# Sheet2.net
KiCad netlist of a schematic drawn in Altium Designer
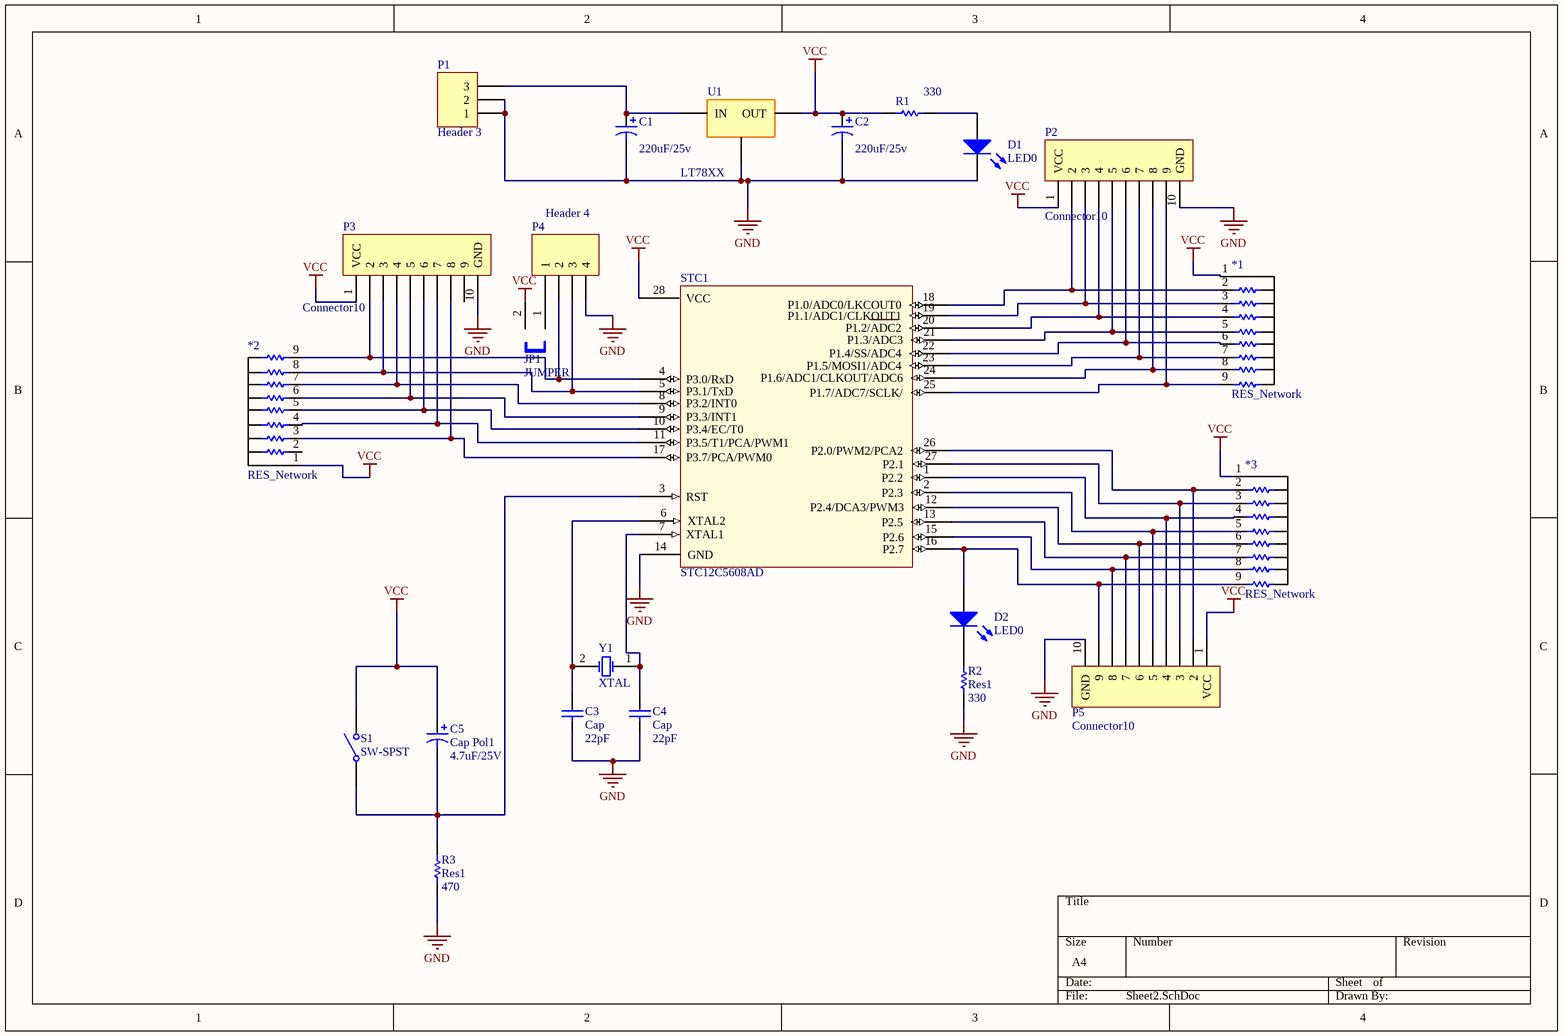
[diagram p0: Sheet2.SchDoc]

(export (version "E")
  (design (tool "Eeschema 10.0.6"))
  (components
    (comp (ref "*1")
      (value "RES_Network")
      (footprint "RES_Network")
      (libsource (lib "Schlib2") (part "RES_Network"))
    )
    (comp (ref "*2")
      (value "RES_Network")
      (footprint "RES_Network")
      (libsource (lib "Schlib2") (part "RES_Network"))
    )
    (comp (ref "*3")
      (value "RES_Network")
      (footprint "RES_Network")
      (libsource (lib "Schlib2") (part "RES_Network"))
    )
    (comp (ref "C1")
      (value "220uF/25v")
      (footprint "CAPA2.5EB")
      (description "Polarized Capacitor (Surface Mount)")
      (fields (field (name "Comment") "Cap Pol3") (field (name "PUBLISHER") "Altium Limited"))
      (libsource (lib "Miscellaneous Devices") (part "Cap Pol3"))
    )
    (comp (ref "C2")
      (value "220uF/25v")
      (footprint "CAPA2.5EB")
      (description "Polarized Capacitor (Surface Mount)")
      (fields (field (name "Comment") "Cap Pol3") (field (name "PUBLISHER") "Altium Limited"))
      (libsource (lib "Miscellaneous Devices") (part "Cap Pol3"))
    )
    (comp (ref "C3")
      (value "Cap")
      (footprint "cap2.5mmceramic")
      (description "Capacitor")
      (fields (field (name "ALTIUM_VALUE") "22pF") (field (name "PUBLISHER") "Altium Limited"))
      (libsource (lib "Miscellaneous Devices") (part "Cap"))
    )
    (comp (ref "C4")
      (value "Cap")
      (footprint "cap2.5mmceramic")
      (description "Capacitor")
      (fields (field (name "ALTIUM_VALUE") "22pF") (field (name "PUBLISHER") "Altium Limited"))
      (libsource (lib "Miscellaneous Devices") (part "Cap"))
    )
    (comp (ref "C5")
      (value "Cap Pol1")
      (footprint "CAPA2.5EBR")
      (description "Polarized Capacitor (Radial)")
      (fields (field (name "ALTIUM_VALUE") "4.7uF/25V") (field (name "PUBLISHER") "Altium Limited"))
      (libsource (lib "Miscellaneous Devices") (part "Cap Pol1"))
    )
    (comp (ref "D1")
      (value "LED0")
      (footprint "ledgreen")
      (description "Typical INFRARED GaAs LED")
      (fields (field (name "PUBLISHER") "Altium Limited"))
      (libsource (lib "Miscellaneous Devices") (part "LED0"))
    )
    (comp (ref "D2")
      (value "LED0")
      (footprint "ledred")
      (description "Typical INFRARED GaAs LED")
      (fields (field (name "PUBLISHER") "Altium Limited"))
      (libsource (lib "Miscellaneous Devices") (part "LED0"))
    )
    (comp (ref "JP1")
      (value "JUMPER")
      (footprint "Jumper_1X2_Black")
      (description "Jumper")
      (libsource (lib "Jumpers") (part "JUMPER"))
    )
    (comp (ref "P1")
      (value "Header 3")
      (footprint "HDR1X3_MTA")
      (description "Header, 3-Pin")
      (fields (field (name "PUBLISHER") "Altium Limited"))
      (libsource (lib "Miscellaneous Connectors") (part "Header 3"))
    )
    (comp (ref "P2")
      (value "Connector10")
      (footprint "pin10")
      (description "Header, 10-Pin")
      (fields (field (name "PUBLISHER") "Altium Limited"))
      (libsource (lib "") (part "Connector10_1"))
    )
    (comp (ref "P3")
      (value "Connector10")
      (footprint "pin10")
      (description "Header, 10-Pin")
      (fields (field (name "PUBLISHER") "Altium Limited"))
      (libsource (lib "") (part "Connector10_1"))
    )
    (comp (ref "P4")
      (value "Header 4")
      (footprint "HDR1X4_MTA")
      (description "Header, 4-Pin")
      (fields (field (name "PUBLISHER") "Altium Limited"))
      (libsource (lib "Miscellaneous Connectors") (part "Header 4"))
    )
    (comp (ref "P5")
      (value "Connector10")
      (footprint "pin10")
      (description "Header, 10-Pin")
      (fields (field (name "PUBLISHER") "Altium Limited"))
      (libsource (lib "Schlib2") (part "Connector10"))
    )
    (comp (ref "R1")
      (value "330")
      (footprint "RES-")
      (description "Resistor")
      (fields (field (name "Comment") "Res1") (field (name "PUBLISHER") "Altium Limited"))
      (libsource (lib "Miscellaneous Devices") (part "Res1"))
    )
    (comp (ref "R2")
      (value "Res1")
      (footprint "RES-")
      (description "Resistor")
      (fields (field (name "ALTIUM_VALUE") "330") (field (name "PUBLISHER") "Altium Limited"))
      (libsource (lib "Miscellaneous Devices") (part "Res1"))
    )
    (comp (ref "R3")
      (value "Res1")
      (footprint "RES-")
      (description "Resistor")
      (fields (field (name "ALTIUM_VALUE") "470") (field (name "PUBLISHER") "Altium Limited"))
      (libsource (lib "Miscellaneous Devices") (part "Res1"))
    )
    (comp (ref "S1")
      (value "SW-SPST")
      (footprint "switchbutton")
      (description "Single-Pole, Single-Throw Switch")
      (fields (field (name "PUBLISHER") "Altium Limited"))
      (libsource (lib "Miscellaneous Devices") (part "SW-SPST"))
    )
    (comp (ref "STC1")
      (value "STC12C5608AD")
      (footprint "SO28_M")
      (libsource (lib "Schlib2") (part "STC12C5608AD"))
    )
    (comp (ref "U1") (value "LT78XX") (footprint "to220ab") (libsource (lib "LOEITECH Device") (part "78XX")))
    (comp (ref "Y1")
      (value "XTAL")
      (footprint "Crystal")
      (description "Crystal Oscillator")
      (fields (field (name "PUBLISHER") "Altium Limited"))
      (libsource (lib "Miscellaneous Devices") (part "XTAL"))
    )
  )
  (nets
    (net (code "1") (name "GND") (class "Default")
      (node (ref "C1") (pin "2") (pinfunction "2_2") (pintype "passive"))
      (node (ref "C2") (pin "2") (pinfunction "2_2") (pintype "passive"))
      (node (ref "C3") (pin "1") (pinfunction "1_1") (pintype "passive"))
      (node (ref "C4") (pin "1") (pinfunction "1_1") (pintype "passive"))
      (node (ref "D1") (pin "2") (pinfunction "K_2") (pintype "passive"))
      (node (ref "P1") (pin "1") (pinfunction "1_1") (pintype "passive"))
      (node (ref "P1") (pin "2") (pinfunction "2_2") (pintype "passive"))
      (node (ref "P2") (pin "10") (pinfunction "GND_10") (pintype "passive"))
      (node (ref "P3") (pin "10") (pinfunction "GND_10") (pintype "passive"))
      (node (ref "P4") (pin "4") (pinfunction "4_4") (pintype "passive"))
      (node (ref "P5") (pin "10") (pinfunction "GND_10") (pintype "passive"))
      (node (ref "R2") (pin "1") (pinfunction "1_1") (pintype "passive"))
      (node (ref "R3") (pin "1") (pinfunction "1_1") (pintype "passive"))
      (node (ref "STC1") (pin "14") (pinfunction "GND_14") (pintype "power_in"))
      (node (ref "U1") (pin "2") (pinfunction "GND_2") (pintype "passive"))
    )
    (net (code "2") (name "Net-(D1-A)") (class "Default")
      (node (ref "D1") (pin "1") (pinfunction "A_1") (pintype "passive"))
      (node (ref "R1") (pin "2") (pinfunction "2_2") (pintype "passive"))
    )
    (net (code "3") (name "Net-(D2-A)") (class "Default")
      (node (ref "*3") (pin "9") (pinfunction "1_9") (pintype "passive"))
      (node (ref "D2") (pin "1") (pinfunction "A_1") (pintype "passive"))
      (node (ref "P5") (pin "9") (pinfunction "9_9") (pintype "passive"))
      (node (ref "STC1") (pin "16") (pinfunction "P2.7_16") (pintype "bidirectional"))
    )
    (net (code "4") (name "Net-(D2-K)") (class "Default")
      (node (ref "D2") (pin "2") (pinfunction "K_2") (pintype "passive"))
      (node (ref "R2") (pin "2") (pinfunction "2_2") (pintype "passive"))
    )
    (net (code "5") (name "Net-(JP1-Pad1)") (class "Default")
      (node (ref "JP1") (pin "1") (pinfunction "1_1") (pintype "passive"))
      (node (ref "P4") (pin "1") (pinfunction "1_1") (pintype "passive"))
    )
    (net (code "6") (name "Net-(S1-COMMON)") (class "Default")
      (node (ref "C5") (pin "2") (pinfunction "2_2") (pintype "passive"))
      (node (ref "R3") (pin "2") (pinfunction "2_2") (pintype "passive"))
      (node (ref "S1") (pin "1") (pinfunction "COMMON_1") (pintype "passive"))
      (node (ref "STC1") (pin "3") (pinfunction "RST_3") (pintype "input"))
    )
    (net (code "7") (name "Net-(STC1-P1.0{slash}ADC0{slash}LKCOUT0)") (class "Default")
      (node (ref "*1") (pin "2") (pinfunction "1_2") (pintype "passive"))
      (node (ref "P2") (pin "2") (pinfunction "2_2") (pintype "passive"))
      (node (ref "STC1") (pin "18") (pinfunction "P1.0/ADC0/LKCOUT0_18") (pintype "bidirectional"))
    )
    (net (code "8") (name "Net-(STC1-P1.1{slash}ADC1{slash}CLKOUT1)") (class "Default")
      (node (ref "*1") (pin "3") (pinfunction "1_3") (pintype "passive"))
      (node (ref "P2") (pin "3") (pinfunction "3_3") (pintype "passive"))
      (node (ref "STC1") (pin "19") (pinfunction "P1.1/ADC1/CLKOUT1_19") (pintype "bidirectional"))
    )
    (net (code "9") (name "Net-(STC1-P1.2{slash}ADC2)") (class "Default")
      (node (ref "*1") (pin "4") (pinfunction "1_4") (pintype "passive"))
      (node (ref "P2") (pin "4") (pinfunction "4_4") (pintype "passive"))
      (node (ref "STC1") (pin "20") (pinfunction "P1.2/ADC2_20") (pintype "bidirectional"))
    )
    (net (code "10") (name "Net-(STC1-P1.3{slash}ADC3)") (class "Default")
      (node (ref "*1") (pin "5") (pinfunction "1_5") (pintype "passive"))
      (node (ref "P2") (pin "5") (pinfunction "5_5") (pintype "passive"))
      (node (ref "STC1") (pin "21") (pinfunction "P1.3/ADC3_21") (pintype "bidirectional"))
    )
    (net (code "11") (name "Net-(STC1-P1.4{slash}SS{slash}ADC4)") (class "Default")
      (node (ref "*1") (pin "6") (pinfunction "1_6") (pintype "passive"))
      (node (ref "P2") (pin "6") (pinfunction "6_6") (pintype "passive"))
      (node (ref "STC1") (pin "22") (pinfunction "P1.4/SS/ADC4_22") (pintype "bidirectional"))
    )
    (net (code "12") (name "Net-(STC1-P1.5{slash}MOSI1{slash}ADC4)") (class "Default")
      (node (ref "*1") (pin "7") (pinfunction "1_7") (pintype "passive"))
      (node (ref "P2") (pin "7") (pinfunction "7_7") (pintype "passive"))
      (node (ref "STC1") (pin "23") (pinfunction "P1.5/MOSI1/ADC4_23") (pintype "bidirectional"))
    )
    (net (code "13") (name "Net-(STC1-P1.6{slash}ADC1{slash}CLKOUT{slash}ADC6)") (class "Default")
      (node (ref "*1") (pin "8") (pinfunction "1_8") (pintype "passive"))
      (node (ref "P2") (pin "8") (pinfunction "8_8") (pintype "passive"))
      (node (ref "STC1") (pin "24") (pinfunction "P1.6/ADC1/CLKOUT/ADC6_24") (pintype "bidirectional"))
    )
    (net (code "14") (name "Net-(STC1-P1.7{slash}ADC7{slash}SCLK{slash})") (class "Default")
      (node (ref "*1") (pin "9") (pinfunction "1_9") (pintype "passive"))
      (node (ref "P2") (pin "9") (pinfunction "9_9") (pintype "passive"))
      (node (ref "STC1") (pin "25") (pinfunction "P1.7/ADC7/SCLK/_25") (pintype "bidirectional"))
    )
    (net (code "15") (name "Net-(STC1-P2.0{slash}PWM2{slash}PCA2)") (class "Default")
      (node (ref "*3") (pin "2") (pinfunction "1_2") (pintype "passive"))
      (node (ref "P5") (pin "2") (pinfunction "2_2") (pintype "passive"))
      (node (ref "STC1") (pin "26") (pinfunction "P2.0/PWM2/PCA2_26") (pintype "bidirectional"))
    )
    (net (code "16") (name "Net-(STC1-P2.1)") (class "Default")
      (node (ref "*3") (pin "3") (pinfunction "1_3") (pintype "passive"))
      (node (ref "P5") (pin "3") (pinfunction "3_3") (pintype "passive"))
      (node (ref "STC1") (pin "27") (pinfunction "P2.1_27") (pintype "bidirectional"))
    )
    (net (code "17") (name "Net-(STC1-P2.2)") (class "Default")
      (node (ref "*3") (pin "4") (pinfunction "1_4") (pintype "passive"))
      (node (ref "P5") (pin "4") (pinfunction "4_4") (pintype "passive"))
      (node (ref "STC1") (pin "1") (pinfunction "P2.2_1") (pintype "bidirectional"))
    )
    (net (code "18") (name "Net-(STC1-P2.3)") (class "Default")
      (node (ref "*3") (pin "5") (pinfunction "1_5") (pintype "passive"))
      (node (ref "P5") (pin "5") (pinfunction "5_5") (pintype "passive"))
      (node (ref "STC1") (pin "2") (pinfunction "P2.3_2") (pintype "bidirectional"))
    )
    (net (code "19") (name "Net-(STC1-P2.4{slash}DCA3{slash}PWM3)") (class "Default")
      (node (ref "*3") (pin "6") (pinfunction "1_6") (pintype "passive"))
      (node (ref "P5") (pin "6") (pinfunction "6_6") (pintype "passive"))
      (node (ref "STC1") (pin "12") (pinfunction "P2.4/DCA3/PWM3_12") (pintype "bidirectional"))
    )
    (net (code "20") (name "Net-(STC1-P2.5)") (class "Default")
      (node (ref "*3") (pin "7") (pinfunction "1_7") (pintype "passive"))
      (node (ref "P5") (pin "7") (pinfunction "7_7") (pintype "passive"))
      (node (ref "STC1") (pin "13") (pinfunction "P2.5_13") (pintype "bidirectional"))
    )
    (net (code "21") (name "Net-(STC1-P2.6)") (class "Default")
      (node (ref "*3") (pin "8") (pinfunction "1_8") (pintype "passive"))
      (node (ref "P5") (pin "8") (pinfunction "8_8") (pintype "passive"))
      (node (ref "STC1") (pin "15") (pinfunction "P2.6_15") (pintype "bidirectional"))
    )
    (net (code "22") (name "Net-(STC1-P3.0{slash}RxD)") (class "Default")
      (node (ref "*2") (pin "9") (pinfunction "1_9") (pintype "passive"))
      (node (ref "P3") (pin "2") (pinfunction "2_2") (pintype "passive"))
      (node (ref "P4") (pin "2") (pinfunction "2_2") (pintype "passive"))
      (node (ref "STC1") (pin "4") (pinfunction "P3.0/RxD_4") (pintype "bidirectional"))
    )
    (net (code "23") (name "Net-(STC1-P3.1{slash}TxD)") (class "Default")
      (node (ref "*2") (pin "8") (pinfunction "1_8") (pintype "passive"))
      (node (ref "P3") (pin "3") (pinfunction "3_3") (pintype "passive"))
      (node (ref "P4") (pin "3") (pinfunction "3_3") (pintype "passive"))
      (node (ref "STC1") (pin "5") (pinfunction "P3.1/TxD_5") (pintype "bidirectional"))
    )
    (net (code "24") (name "Net-(STC1-P3.2{slash}INT0)") (class "Default")
      (node (ref "*2") (pin "7") (pinfunction "1_7") (pintype "passive"))
      (node (ref "P3") (pin "4") (pinfunction "4_4") (pintype "passive"))
      (node (ref "STC1") (pin "8") (pinfunction "P3.2/INT0_8") (pintype "bidirectional"))
    )
    (net (code "25") (name "Net-(STC1-P3.3{slash}INT1)") (class "Default")
      (node (ref "*2") (pin "6") (pinfunction "1_6") (pintype "passive"))
      (node (ref "P3") (pin "5") (pinfunction "5_5") (pintype "passive"))
      (node (ref "STC1") (pin "9") (pinfunction "P3.3/INT1_9") (pintype "bidirectional"))
    )
    (net (code "26") (name "Net-(STC1-P3.4{slash}EC{slash}T0)") (class "Default")
      (node (ref "*2") (pin "5") (pinfunction "1_5") (pintype "passive"))
      (node (ref "P3") (pin "6") (pinfunction "6_6") (pintype "passive"))
      (node (ref "STC1") (pin "10") (pinfunction "P3.4/EC/T0_10") (pintype "bidirectional"))
    )
    (net (code "27") (name "Net-(STC1-P3.5{slash}T1{slash}PCA{slash}PWM1)") (class "Default")
      (node (ref "*2") (pin "4") (pinfunction "1_4") (pintype "passive"))
      (node (ref "P3") (pin "7") (pinfunction "7_7") (pintype "passive"))
      (node (ref "STC1") (pin "11") (pinfunction "P3.5/T1/PCA/PWM1_11") (pintype "bidirectional"))
    )
    (net (code "28") (name "Net-(STC1-P3.7{slash}PCA{slash}PWM0)") (class "Default")
      (node (ref "*2") (pin "3") (pinfunction "1_3") (pintype "passive"))
      (node (ref "P3") (pin "8") (pinfunction "8_8") (pintype "passive"))
      (node (ref "STC1") (pin "17") (pinfunction "P3.7/PCA/PWM0_17") (pintype "bidirectional"))
    )
    (net (code "29") (name "Net-(STC1-XTAL1)") (class "Default")
      (node (ref "C4") (pin "2") (pinfunction "2_2") (pintype "passive"))
      (node (ref "STC1") (pin "7") (pinfunction "XTAL1_7") (pintype "input"))
      (node (ref "Y1") (pin "1") (pinfunction "OSC1_1") (pintype "passive"))
    )
    (net (code "30") (name "Net-(STC1-XTAL2)") (class "Default")
      (node (ref "C3") (pin "2") (pinfunction "2_2") (pintype "passive"))
      (node (ref "STC1") (pin "6") (pinfunction "XTAL2_6") (pintype "input"))
      (node (ref "Y1") (pin "2") (pinfunction "OSC2_2") (pintype "passive"))
    )
    (net (code "31") (name "Net-(U1-IN)") (class "Default")
      (node (ref "C1") (pin "1") (pinfunction "1_1") (pintype "passive"))
      (node (ref "P1") (pin "3") (pinfunction "3_3") (pintype "passive"))
      (node (ref "U1") (pin "1") (pinfunction "IN_1") (pintype "passive"))
    )
    (net (code "32") (name "VCC") (class "Default")
      (node (ref "*1") (pin "1") (pinfunction "1_1") (pintype "passive"))
      (node (ref "*2") (pin "1") (pinfunction "1_1") (pintype "passive"))
      (node (ref "*3") (pin "1") (pinfunction "1_1") (pintype "passive"))
      (node (ref "C2") (pin "1") (pinfunction "1_1") (pintype "passive"))
      (node (ref "C5") (pin "1") (pinfunction "1_1") (pintype "passive"))
      (node (ref "JP1") (pin "2") (pinfunction "2_2") (pintype "passive"))
      (node (ref "P2") (pin "1") (pinfunction "VCC_1") (pintype "passive"))
      (node (ref "P3") (pin "1") (pinfunction "VCC_1") (pintype "passive"))
      (node (ref "P5") (pin "1") (pinfunction "VCC_1") (pintype "passive"))
      (node (ref "R1") (pin "1") (pinfunction "1_1") (pintype "passive"))
      (node (ref "S1") (pin "2") (pinfunction "NO_2") (pintype "passive"))
      (node (ref "STC1") (pin "28") (pinfunction "VCC_28") (pintype "power_in"))
      (node (ref "U1") (pin "3") (pinfunction "OUT_3") (pintype "passive"))
    )
    (net (code "33") (name "unconnected-(*1-Pad2)") (class "Default")
      (node (ref "*1") (pin "2") (pinfunction "2_2") (pintype "passive"))
    )
    (net (code "34") (name "unconnected-(*1-Pad2)_1") (class "Default")
      (node (ref "*1") (pin "2") (pinfunction "2_2") (pintype "passive"))
    )
    (net (code "35") (name "unconnected-(*1-Pad2)_2") (class "Default")
      (node (ref "*1") (pin "2") (pinfunction "2_2") (pintype "passive"))
    )
    (net (code "36") (name "unconnected-(*1-Pad2)_3") (class "Default")
      (node (ref "*1") (pin "2") (pinfunction "2_2") (pintype "passive"))
    )
    (net (code "37") (name "unconnected-(*1-Pad2)_4") (class "Default")
      (node (ref "*1") (pin "2") (pinfunction "2_2") (pintype "passive"))
    )
    (net (code "38") (name "unconnected-(*1-Pad2)_5") (class "Default")
      (node (ref "*1") (pin "2") (pinfunction "2_2") (pintype "passive"))
    )
    (net (code "39") (name "unconnected-(*1-Pad2)_6") (class "Default")
      (node (ref "*1") (pin "2") (pinfunction "2_2") (pintype "passive"))
    )
    (net (code "40") (name "unconnected-(*1-Pad2)_7") (class "Default")
      (node (ref "*1") (pin "2") (pinfunction "2_2") (pintype "passive"))
    )
    (net (code "41") (name "unconnected-(*1-Pad2)_8") (class "Default")
      (node (ref "*1") (pin "2") (pinfunction "2_2") (pintype "passive"))
    )
    (net (code "42") (name "unconnected-(*2-1-Pad2)") (class "Default")
      (node (ref "*2") (pin "2") (pinfunction "1_2") (pintype "passive"))
    )
    (net (code "43") (name "unconnected-(*2-Pad2)") (class "Default")
      (node (ref "*2") (pin "2") (pinfunction "2_2") (pintype "passive"))
    )
    (net (code "44") (name "unconnected-(*2-Pad2)_1") (class "Default")
      (node (ref "*2") (pin "2") (pinfunction "2_2") (pintype "passive"))
    )
    (net (code "45") (name "unconnected-(*2-Pad2)_2") (class "Default")
      (node (ref "*2") (pin "2") (pinfunction "2_2") (pintype "passive"))
    )
    (net (code "46") (name "unconnected-(*2-Pad2)_3") (class "Default")
      (node (ref "*2") (pin "2") (pinfunction "2_2") (pintype "passive"))
    )
    (net (code "47") (name "unconnected-(*2-Pad2)_4") (class "Default")
      (node (ref "*2") (pin "2") (pinfunction "2_2") (pintype "passive"))
    )
    (net (code "48") (name "unconnected-(*2-Pad2)_5") (class "Default")
      (node (ref "*2") (pin "2") (pinfunction "2_2") (pintype "passive"))
    )
    (net (code "49") (name "unconnected-(*2-Pad2)_6") (class "Default")
      (node (ref "*2") (pin "2") (pinfunction "2_2") (pintype "passive"))
    )
    (net (code "50") (name "unconnected-(*2-Pad2)_7") (class "Default")
      (node (ref "*2") (pin "2") (pinfunction "2_2") (pintype "passive"))
    )
    (net (code "51") (name "unconnected-(*2-Pad2)_8") (class "Default")
      (node (ref "*2") (pin "2") (pinfunction "2_2") (pintype "passive"))
    )
    (net (code "52") (name "unconnected-(*3-Pad2)") (class "Default")
      (node (ref "*3") (pin "2") (pinfunction "2_2") (pintype "passive"))
    )
    (net (code "53") (name "unconnected-(*3-Pad2)_1") (class "Default")
      (node (ref "*3") (pin "2") (pinfunction "2_2") (pintype "passive"))
    )
    (net (code "54") (name "unconnected-(*3-Pad2)_2") (class "Default")
      (node (ref "*3") (pin "2") (pinfunction "2_2") (pintype "passive"))
    )
    (net (code "55") (name "unconnected-(*3-Pad2)_3") (class "Default")
      (node (ref "*3") (pin "2") (pinfunction "2_2") (pintype "passive"))
    )
    (net (code "56") (name "unconnected-(*3-Pad2)_4") (class "Default")
      (node (ref "*3") (pin "2") (pinfunction "2_2") (pintype "passive"))
    )
    (net (code "57") (name "unconnected-(*3-Pad2)_5") (class "Default")
      (node (ref "*3") (pin "2") (pinfunction "2_2") (pintype "passive"))
    )
    (net (code "58") (name "unconnected-(*3-Pad2)_6") (class "Default")
      (node (ref "*3") (pin "2") (pinfunction "2_2") (pintype "passive"))
    )
    (net (code "59") (name "unconnected-(*3-Pad2)_7") (class "Default")
      (node (ref "*3") (pin "2") (pinfunction "2_2") (pintype "passive"))
    )
    (net (code "60") (name "unconnected-(*3-Pad2)_8") (class "Default")
      (node (ref "*3") (pin "2") (pinfunction "2_2") (pintype "passive"))
    )
    (net (code "61") (name "unconnected-(P3-Pad9)") (class "Default")
      (node (ref "P3") (pin "9") (pinfunction "9_9") (pintype "passive"))
    )
  )
)
